# LCD_SD.net
KiCad netlist of a schematic drawn in Altium Designer
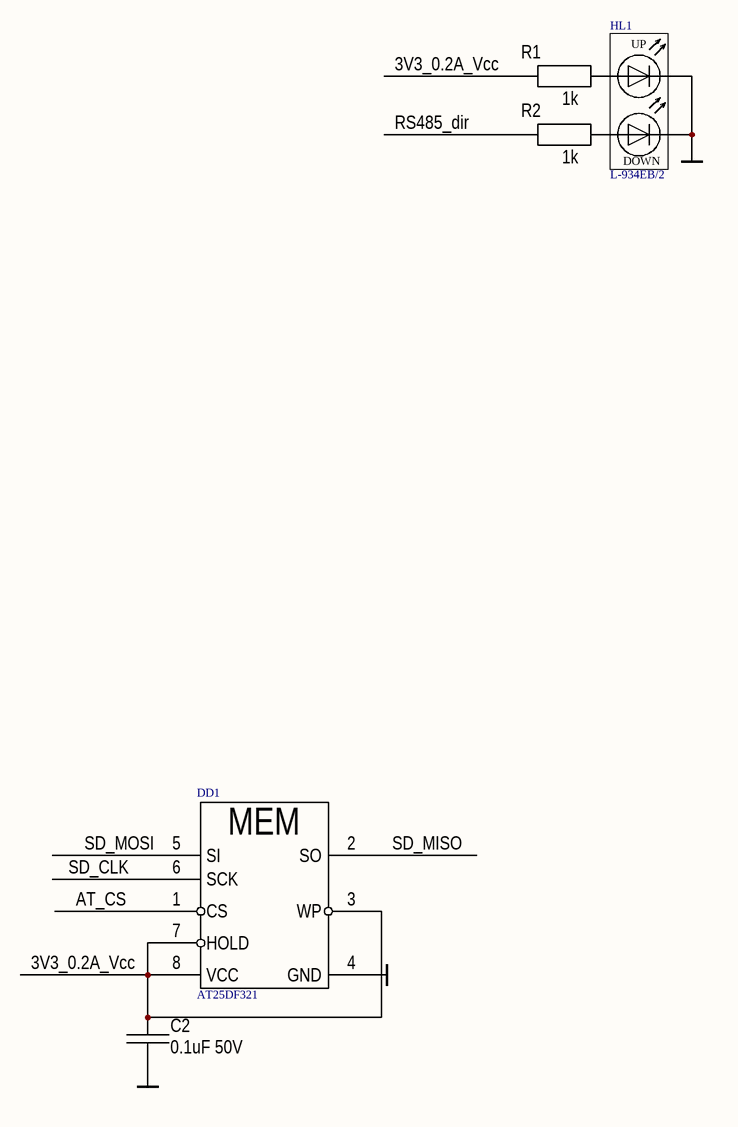
[diagram p0: LCD_SD.SchDoc]

(export (version "E")
  (design (tool "Eeschema 10.0.6"))
  (components
    (comp (ref "C2")
      (value "0.1uF 50V")
      (footprint "0805_CAP")
      (libsource (lib "Integrated_Library_tikhovikt") (part "Cap_np"))
    )
    (comp (ref "DD1")
      (value "AT25DF321")
      (footprint "soic8-200")
      (libsource (lib "Integrated_Library_tikhovikt") (part "AT25DF321"))
    )
    (comp (ref "HL1")
      (value "L-934EB/2")
      (footprint "L-934EB/2")
      (libsource (lib "Integrated_Library_tikhovikt") (part "LEDx2"))
    )
    (comp (ref "R1")
      (value "1k")
      (footprint "0805_RES")
      (libsource (lib "Integrated_Library_tikhovikt") (part "Res"))
    )
    (comp (ref "R2")
      (value "1k")
      (footprint "0805_RES")
      (libsource (lib "Integrated_Library_tikhovikt") (part "Res"))
    )
  )
  (nets
    (net (code "1") (name "/3V3_0.2A_Vcc") (class "Default")
      (node (ref "C2") (pin "1") (pinfunction "1_1") (pintype "passive"))
      (node (ref "DD1") (pin "3") (pinfunction "WP_3") (pintype "passive"))
      (node (ref "DD1") (pin "7") (pinfunction "HOLD_7") (pintype "passive"))
      (node (ref "DD1") (pin "8") (pinfunction "VCC_8") (pintype "passive"))
      (node (ref "R1") (pin "2") (pinfunction "2_2") (pintype "passive"))
    )
    (net (code "2") (name "/AT_CS") (class "Default")
      (node (ref "DD1") (pin "1") (pinfunction "CS_1") (pintype "passive"))
    )
    (net (code "3") (name "/RS485_dir") (class "Default")
      (node (ref "R2") (pin "2") (pinfunction "2_2") (pintype "passive"))
    )
    (net (code "4") (name "/SD_CLK") (class "Default")
      (node (ref "DD1") (pin "6") (pinfunction "SCK_6") (pintype "passive"))
    )
    (net (code "5") (name "/SD_MISO") (class "Default")
      (node (ref "DD1") (pin "2") (pinfunction "SO_2") (pintype "passive"))
    )
    (net (code "6") (name "/SD_MOSI") (class "Default")
      (node (ref "DD1") (pin "5") (pinfunction "SI_5") (pintype "passive"))
    )
    (net (code "7") (name "GND") (class "Default")
      (node (ref "C2") (pin "2") (pinfunction "2_2") (pintype "passive"))
      (node (ref "DD1") (pin "4") (pinfunction "GND_4") (pintype "passive"))
      (node (ref "HL1") (pin "1") (pinfunction "1_1") (pintype "passive"))
      (node (ref "HL1") (pin "3") (pinfunction "3_3") (pintype "passive"))
    )
    (net (code "8") (name "Net-(HL1-Pad2)") (class "Default")
      (node (ref "HL1") (pin "2") (pinfunction "2_2") (pintype "passive"))
      (node (ref "R2") (pin "1") (pinfunction "1_1") (pintype "passive"))
    )
    (net (code "9") (name "Net-(HL1-Pad4)") (class "Default")
      (node (ref "HL1") (pin "4") (pinfunction "4_4") (pintype "passive"))
      (node (ref "R1") (pin "1") (pinfunction "1_1") (pintype "passive"))
    )
  )
)
